# Power_Management.net
KiCad netlist of a schematic drawn in Altium Designer
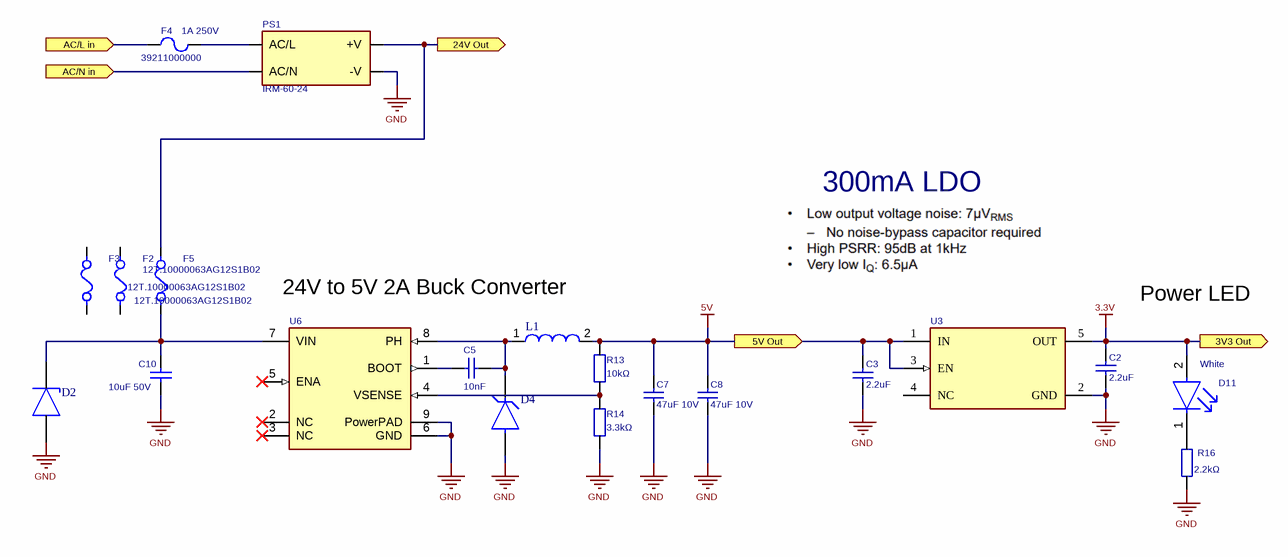
[diagram p0: Power Management.SchDoc]

(export (version "E")
  (design (tool "Eeschema 10.0.6"))
  (components
    (comp (ref "C2")
      (value "2.2uF")
      (footprint "CAPC1005X05N")
      (libsource (lib "SchematicLibrary") (part "SMD_Cap"))
    )
    (comp (ref "C3")
      (value "2.2uF")
      (footprint "CAPC1005X05N")
      (libsource (lib "SchematicLibrary") (part "SMD_Cap"))
    )
    (comp (ref "C5")
      (value "10nF")
      (footprint "CAPC1005X05N")
      (libsource (lib "SchematicLibrary") (part "SMD_Cap"))
    )
    (comp (ref "C7")
      (value "47uF 10V")
      (footprint "CAPC3216X16N")
      (libsource (lib "SchematicLibrary") (part "SMD_Cap"))
    )
    (comp (ref "C8")
      (value "47uF 10V")
      (footprint "CAPC3216X16N")
      (libsource (lib "SchematicLibrary") (part "SMD_Cap"))
    )
    (comp (ref "C10")
      (value "10uF 50V")
      (footprint "CAPC3216X16N")
      (libsource (lib "Miscellaneous Devices") (part "CAP-NP-2"))
    )
    (comp (ref "D2")
      (value "~")
      (footprint "SOD-123FL")
      (fields (field (name "MPN") "SMF24A"))
      (libsource (lib "Miscellaneous Connectors") (part "d386f69c7d770905792c16b93fa31a7"))
    )
    (comp (ref "D4")
      (value "~")
      (footprint "SOD-123")
      (description "BZT52C20-7-F BZT52C20 Series 20 V 10 mA 500 mW Surface Mount Zener Diode - SOD-123")
      (fields (field (name "MPN") "B5819W SL") (field (name "JLCPCB PART #") "C8598"))
      (libsource (lib "Miscellaneous Devices") (part "f813f71cba58e380607f5dd3caf9714"))
    )
    (comp (ref "D11")
      (value "White")
      (footprint "LEDC1608X08N")
      (description "LED")
      (libsource (lib "Redako") (part "8706943c75ba83719d021d2fdc84c58"))
    )
    (comp (ref "F2")
      (value "~")
      (footprint "FP-SF-1206S-IPC_B")
      (description "FUSE BOARD MOUNT 1A 63VDC 1206")
      (fields (field (name "MPN") "12T.10000063AG12S1B02"))
      (libsource (lib "Altium Content Vault") (part "5bcf9b9f640e542cf0359d10258e979"))
    )
    (comp (ref "F3")
      (value "~")
      (footprint "FP-SF-1206S-IPC_B")
      (description "FUSE BOARD MOUNT 1A 63VDC 1206")
      (fields (field (name "MPN") "12T.10000063AG12S1B02"))
      (libsource (lib "Altium Content Vault") (part "5bcf9b9f640e542cf0359d10258e979"))
    )
    (comp (ref "F4")
      (value "1A 250V")
      (footprint "FUS_LITTELFUSE_392_LTF")
      (fields
        (field (name "MPN") "39211000000")
        (field (name "MANUFACTURER") "Littelfuse")
        (field (name "JLCPCB PART #") "C99566")
      )
      (libsource (lib "Redako") (part "FUSE-2"))
    )
    (comp (ref "F5")
      (value "~")
      (footprint "FP-SF-1206S-IPC_B")
      (description "FUSE BOARD MOUNT 1A 63VDC 1206")
      (fields (field (name "MPN") "12T.10000063AG12S1B02"))
      (libsource (lib "Altium Content Vault") (part "5bcf9b9f640e542cf0359d10258e979"))
    )
    (comp (ref "L1")
      (value "~")
      (footprint "SWPA6054A")
      (description "100uH ±20% 800mA 433mΩ SMD,6.0x6.0x4.5mm Power Inductors RoHS")
      (fields (field (name "MPN") "SWPA6045S101MT") (field (name "JLCPCB PART #") "C60633"))
      (libsource (lib "RedakoJLC") (part "SWPA6045S101MT"))
    )
    (comp (ref "PS1")
      (value "~")
      (footprint "IRM-60-24")
      (description "Enclosed AC DC Converters 1 Uitgang 24V 2.5A 85 ~ 264 VAC Input")
      (fields (field (name "MPN") "IRM-60-24"))
      (libsource (lib "Redako") (part "IRM-60-24"))
    )
    (comp (ref "R13")
      (value "10kΩ")
      (footprint "RESC1005X04N")
      (libsource (lib "SchematicLibrary") (part "Res"))
    )
    (comp (ref "R14")
      (value "3.3kΩ")
      (footprint "RESC1005X04N")
      (libsource (lib "SchematicLibrary") (part "Res"))
    )
    (comp (ref "R16")
      (value "2.2kΩ")
      (footprint "RESC1005X04N")
      (libsource (lib "SchematicLibrary") (part "Res"))
    )
    (comp (ref "U3")
      (value "~")
      (footprint "FP-DBV0005A-MFG")
      (description "IC REG LINEAR 3.3V 300MA SOT23-5")
      (fields (field (name "MPN") "TPS7A2033PDBVR"))
      (libsource (lib "Altium Content Vault") (part "76aa7ad0ceb1012e0d85aeafc53095f"))
    )
    (comp (ref "U6")
      (value "~")
      (footprint "FP-DDA0008J-MFG")
      (description "IC REG BUCK ADJUSTABLE 3A 8SOPWR")
      (fields (field (name "MANUFACTURER") "Texas Instruments") (field (name "MPN") "TPS5430DDAR"))
      (libsource (lib "Altium Content Vault") (part "98da629940cea6febc5630bb55159f3"))
    )
  )
  (nets
    (net (code "1") (name "/24V Out") (class "Default")
      (node (ref "F5") (pin "2") (pinfunction "2_2") (pintype "passive"))
      (node (ref "PS1") (pin "+V") (pinfunction "+V_+V") (pintype "passive"))
    )
    (net (code "2") (name "/AC{slash}L in") (class "Default")
      (node (ref "F4") (pin "1") (pinfunction "1_1") (pintype "passive"))
    )
    (net (code "3") (name "/AC{slash}N in") (class "Default")
      (node (ref "PS1") (pin "AC/N") (pinfunction "AC/N_AC/N") (pintype "passive"))
    )
    (net (code "4") (name "3.3V") (class "Default")
      (node (ref "C2") (pin "2") (pintype "passive"))
      (node (ref "D11") (pin "2") (pinfunction "A_2") (pintype "passive"))
      (node (ref "U3") (pin "5") (pinfunction "OUT_5") (pintype "passive"))
    )
    (net (code "5") (name "5V") (class "Default")
      (node (ref "C3") (pin "2") (pintype "passive"))
      (node (ref "C7") (pin "1") (pintype "passive"))
      (node (ref "C8") (pin "1") (pintype "passive"))
      (node (ref "L1") (pin "2") (pinfunction "2_2") (pintype "passive"))
      (node (ref "R13") (pin "1") (pintype "passive"))
      (node (ref "U3") (pin "1") (pinfunction "IN_1") (pintype "power_in"))
      (node (ref "U3") (pin "3") (pinfunction "EN_3") (pintype "input"))
    )
    (net (code "6") (name "GND") (class "Default")
      (node (ref "C10") (pin "1") (pinfunction "1_1") (pintype "passive"))
      (node (ref "C2") (pin "1") (pintype "passive"))
      (node (ref "C3") (pin "1") (pintype "passive"))
      (node (ref "C7") (pin "2") (pintype "passive"))
      (node (ref "C8") (pin "2") (pintype "passive"))
      (node (ref "D2") (pin "1") (pinfunction "A_1") (pintype "passive"))
      (node (ref "D4") (pin "A") (pinfunction "A_A") (pintype "passive"))
      (node (ref "PS1") (pin "-V") (pinfunction "-V_-V") (pintype "passive"))
      (node (ref "R14") (pin "2") (pintype "passive"))
      (node (ref "R16") (pin "2") (pintype "passive"))
      (node (ref "U3") (pin "2") (pinfunction "GND_2") (pintype "power_in"))
      (node (ref "U6") (pin "6") (pinfunction "GND_6") (pintype "power_in"))
      (node (ref "U6") (pin "9") (pinfunction "PowerPAD_9") (pintype "power_in"))
    )
    (net (code "7") (name "Net-(D2-C)") (class "Default")
      (node (ref "C10") (pin "2") (pinfunction "2_2") (pintype "passive"))
      (node (ref "D2") (pin "2") (pinfunction "C_2") (pintype "passive"))
      (node (ref "F5") (pin "1") (pinfunction "1_1") (pintype "passive"))
      (node (ref "U6") (pin "7") (pinfunction "VIN_7") (pintype "power_in"))
    )
    (net (code "8") (name "Net-(D4-C)") (class "Default")
      (node (ref "C5") (pin "2") (pintype "passive"))
      (node (ref "D4") (pin "K") (pinfunction "C_K") (pintype "passive"))
      (node (ref "L1") (pin "1") (pinfunction "1_1") (pintype "passive"))
      (node (ref "U6") (pin "8") (pinfunction "PH_8") (pintype "input"))
    )
    (net (code "9") (name "Net-(D11-C)") (class "Default")
      (node (ref "D11") (pin "1") (pinfunction "C_1") (pintype "passive"))
      (node (ref "R16") (pin "1") (pintype "passive"))
    )
    (net (code "10") (name "Net-(F4-Pad2)") (class "Default")
      (node (ref "F4") (pin "2") (pinfunction "2_2") (pintype "passive"))
      (node (ref "PS1") (pin "AC/L") (pinfunction "AC/L_AC/L") (pintype "passive"))
    )
    (net (code "11") (name "Net-(U6-BOOT)") (class "Default")
      (node (ref "C5") (pin "1") (pintype "passive"))
      (node (ref "U6") (pin "1") (pinfunction "BOOT_1") (pintype "output"))
    )
    (net (code "12") (name "Net-(U6-VSENSE)") (class "Default")
      (node (ref "R13") (pin "2") (pintype "passive"))
      (node (ref "R14") (pin "1") (pintype "passive"))
      (node (ref "U6") (pin "4") (pinfunction "VSENSE_4") (pintype "input"))
    )
    (net (code "13") (name "unconnected-(F2-Pad1)") (class "Default")
      (node (ref "F2") (pin "1") (pinfunction "1_1") (pintype "passive"))
    )
    (net (code "14") (name "unconnected-(F2-Pad2)") (class "Default")
      (node (ref "F2") (pin "2") (pinfunction "2_2") (pintype "passive"))
    )
    (net (code "15") (name "unconnected-(F3-Pad1)") (class "Default")
      (node (ref "F3") (pin "1") (pinfunction "1_1") (pintype "passive"))
    )
    (net (code "16") (name "unconnected-(F3-Pad2)") (class "Default")
      (node (ref "F3") (pin "2") (pinfunction "2_2") (pintype "passive"))
    )
    (net (code "17") (name "unconnected-(U3-NC-Pad4)") (class "Default")
      (node (ref "U3") (pin "4") (pinfunction "NC_4") (pintype "passive"))
    )
    (net (code "18") (name "unconnected-(U6-ENA-Pad5)") (class "Default")
      (node (ref "U6") (pin "5") (pinfunction "ENA_5") (pintype "input+no_connect"))
    )
    (net (code "19") (name "unconnected-(U6-NC-Pad2)") (class "Default")
      (node (ref "U6") (pin "2") (pinfunction "NC_2") (pintype "passive+no_connect"))
    )
    (net (code "20") (name "unconnected-(U6-NC-Pad3)") (class "Default")
      (node (ref "U6") (pin "3") (pinfunction "NC_3") (pintype "passive+no_connect"))
    )
  )
)
